# theremin.net
KiCad netlist of a schematic drawn in Altium Designer
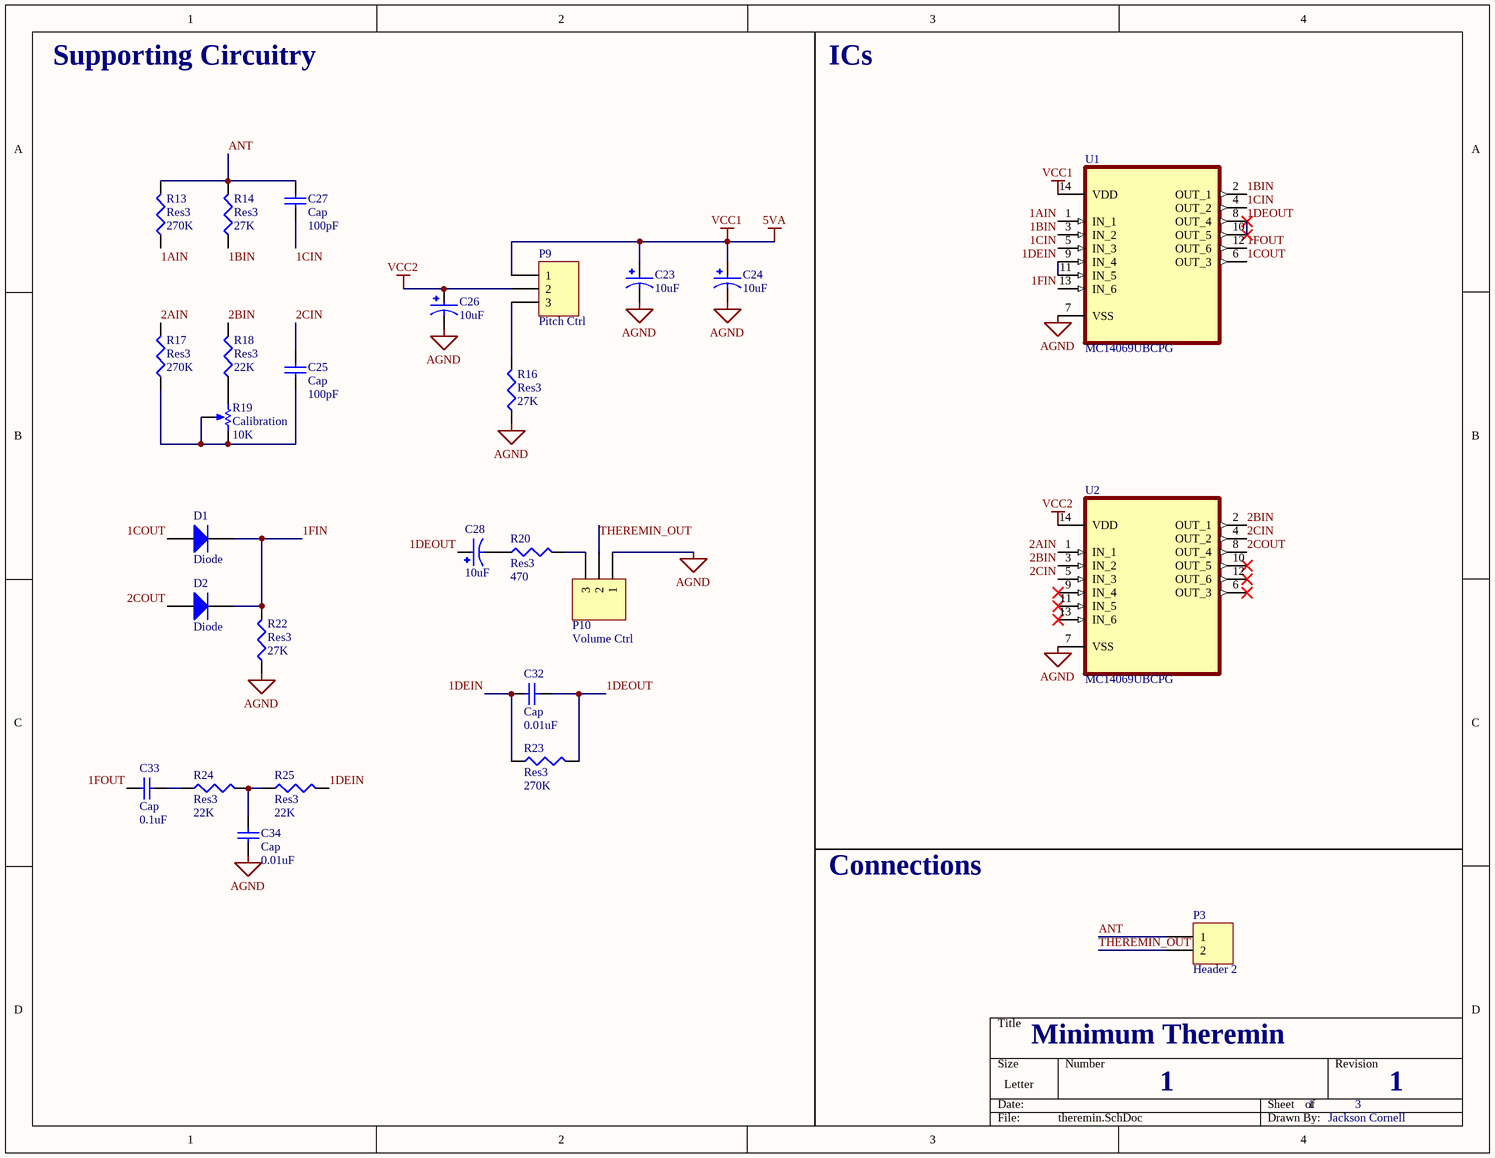
[diagram p0: theremin.SchDoc]

(export (version "E")
  (design (tool "Eeschema 10.0.6"))
  (components
    (comp (ref "C23")
      (value "10uF")
      (footprint "CAPPRD500W60D1000H1250")
      (description "Aluminum Electrolytic Capacitors - Radial Leaded")
      (fields (field (name "MP") "EEU-FC1V221E") (field (name "MF") "Panasonic"))
      (libsource (lib "") (part "EEUFC1V221E_1"))
    )
    (comp (ref "C24")
      (value "10uF")
      (footprint "CAPPRD500W60D1000H1250")
      (description "Aluminum Electrolytic Capacitors - Radial Leaded")
      (fields (field (name "MP") "EEU-FC1V221E") (field (name "MF") "Panasonic"))
      (libsource (lib "") (part "EEUFC1V221E_1"))
    )
    (comp (ref "C25")
      (value "Cap")
      (footprint "Passives:CAPC0805")
      (description "Capacitor")
      (fields (field (name "ALTIUM_VALUE") "100pF") (field (name "PUBLISHER") "Altium Limited"))
      (libsource (lib "Miscellaneous Devices") (part "Cap"))
    )
    (comp (ref "C26")
      (value "10uF")
      (footprint "CAPPRD500W60D1000H1250")
      (description "Aluminum Electrolytic Capacitors - Radial Leaded")
      (fields (field (name "MP") "EEU-FC1V221E") (field (name "MF") "Panasonic"))
      (libsource (lib "") (part "EEUFC1V221E_1"))
    )
    (comp (ref "C27")
      (value "Cap")
      (footprint "Passives:CAPC0805")
      (description "Capacitor")
      (fields (field (name "ALTIUM_VALUE") "100pF") (field (name "PUBLISHER") "Altium Limited"))
      (libsource (lib "Miscellaneous Devices") (part "Cap"))
    )
    (comp (ref "C28")
      (value "10uF")
      (footprint "CAPPRD500W60D1000H1250")
      (description "Aluminum Electrolytic Capacitors - Radial Leaded")
      (fields (field (name "MP") "EEU-FC1V221E") (field (name "MF") "Panasonic"))
      (libsource (lib "EEUFC1V221E") (part "EEUFC1V221E"))
    )
    (comp (ref "C32")
      (value "Cap")
      (footprint "Passives:CAPC0805")
      (description "Capacitor")
      (fields (field (name "ALTIUM_VALUE") "0.01uF") (field (name "PUBLISHER") "Altium Limited"))
      (libsource (lib "Miscellaneous Devices") (part "Cap"))
    )
    (comp (ref "C33")
      (value "Cap")
      (footprint "Passives:CAPC0805")
      (description "Capacitor")
      (fields (field (name "ALTIUM_VALUE") "0.1uF") (field (name "PUBLISHER") "Altium Limited"))
      (libsource (lib "Miscellaneous Devices") (part "Cap"))
    )
    (comp (ref "C34")
      (value "Cap")
      (footprint "Passives:CAPC0805")
      (description "Capacitor")
      (fields (field (name "ALTIUM_VALUE") "0.01uF") (field (name "PUBLISHER") "Altium Limited"))
      (libsource (lib "Miscellaneous Devices") (part "Cap"))
    )
    (comp (ref "D1")
      (value "Diode")
      (footprint "SMC")
      (description "Default Diode")
      (fields (field (name "PUBLISHER") "Altium Limited"))
      (libsource (lib "Miscellaneous Devices") (part "Diode"))
    )
    (comp (ref "D2")
      (value "Diode")
      (footprint "SMC")
      (description "Default Diode")
      (fields (field (name "PUBLISHER") "Altium Limited"))
      (libsource (lib "Miscellaneous Devices") (part "Diode"))
    )
    (comp (ref "P3")
      (value "Header 2")
      (footprint "HDR1X2")
      (description "Header, 2-Pin")
      (fields (field (name "PUBLISHER") "Altium Limited"))
      (libsource (lib "Miscellaneous Connectors") (part "Header 2"))
    )
    (comp (ref "P9")
      (value "Pitch Ctrl")
      (footprint "HDR1X3")
      (description "Header, 3-Pin")
      (fields (field (name "PUBLISHER") "Altium Limited"))
      (libsource (lib "Miscellaneous Connectors") (part "Header 3"))
    )
    (comp (ref "P10")
      (value "Volume Ctrl")
      (footprint "HDR1X3")
      (description "Header, 3-Pin")
      (fields (field (name "PUBLISHER") "Altium Limited"))
      (libsource (lib "") (part "Header 3_1"))
    )
    (comp (ref "R13")
      (value "Res3")
      (footprint "Passives:RES0805")
      (description "Resistor")
      (fields (field (name "ALTIUM_VALUE") "270K") (field (name "PUBLISHER") "Altium Limited"))
      (libsource (lib "Miscellaneous Devices") (part "Res3"))
    )
    (comp (ref "R14")
      (value "Res3")
      (footprint "Passives:RES0805")
      (description "Resistor")
      (fields (field (name "ALTIUM_VALUE") "27K") (field (name "PUBLISHER") "Altium Limited"))
      (libsource (lib "Miscellaneous Devices") (part "Res3"))
    )
    (comp (ref "R16")
      (value "Res3")
      (footprint "Passives:RES0805")
      (description "Resistor")
      (fields (field (name "ALTIUM_VALUE") "27K") (field (name "PUBLISHER") "Altium Limited"))
      (libsource (lib "Miscellaneous Devices") (part "Res3"))
    )
    (comp (ref "R17")
      (value "Res3")
      (footprint "Passives:RES0805")
      (description "Resistor")
      (fields (field (name "ALTIUM_VALUE") "270K") (field (name "PUBLISHER") "Altium Limited"))
      (libsource (lib "Miscellaneous Devices") (part "Res3"))
    )
    (comp (ref "R18")
      (value "Res3")
      (footprint "Passives:RES0805")
      (description "Resistor")
      (fields (field (name "ALTIUM_VALUE") "22K") (field (name "PUBLISHER") "Altium Limited"))
      (libsource (lib "Miscellaneous Devices") (part "Res3"))
    )
    (comp (ref "R19")
      (value "Calibration")
      (footprint "VR5")
      (description "Potentiometer")
      (fields (field (name "ALTIUM_VALUE") "10K") (field (name "PUBLISHER") "Altium Limited"))
      (libsource (lib "Miscellaneous Devices") (part "RPot"))
    )
    (comp (ref "R20")
      (value "Res3")
      (footprint "Passives:RES0805")
      (description "Resistor")
      (fields (field (name "ALTIUM_VALUE") "470") (field (name "PUBLISHER") "Altium Limited"))
      (libsource (lib "Miscellaneous Devices") (part "Res3"))
    )
    (comp (ref "R22")
      (value "Res3")
      (footprint "Passives:RES0805")
      (description "Resistor")
      (fields (field (name "ALTIUM_VALUE") "27K") (field (name "PUBLISHER") "Altium Limited"))
      (libsource (lib "Miscellaneous Devices") (part "Res3"))
    )
    (comp (ref "R23")
      (value "Res3")
      (footprint "Passives:RES0805")
      (description "Resistor")
      (fields (field (name "ALTIUM_VALUE") "270K") (field (name "PUBLISHER") "Altium Limited"))
      (libsource (lib "Miscellaneous Devices") (part "Res3"))
    )
    (comp (ref "R24")
      (value "Res3")
      (footprint "Passives:RES0805")
      (description "Resistor")
      (fields (field (name "ALTIUM_VALUE") "22K") (field (name "PUBLISHER") "Altium Limited"))
      (libsource (lib "Miscellaneous Devices") (part "Res3"))
    )
    (comp (ref "R25")
      (value "Res3")
      (footprint "Passives:RES0805")
      (description "Resistor")
      (fields (field (name "ALTIUM_VALUE") "22K") (field (name "PUBLISHER") "Altium Limited"))
      (libsource (lib "Miscellaneous Devices") (part "Res3"))
    )
    (comp (ref "U1")
      (value "MC14069UBCPG")
      (footprint "DIP254P762X469-14")
      (description "Inverter IC 6 Channel - 14-PDIP")
      (fields (field (name "MF") "ON Semiconductor"))
      (libsource (lib "MC14069UBCPG") (part "MC14069UBCPG"))
    )
    (comp (ref "U2")
      (value "MC14069UBCPG")
      (footprint "DIP254P762X469-14")
      (description "Inverter IC 6 Channel - 14-PDIP")
      (fields (field (name "MF") "ON Semiconductor"))
      (libsource (lib "MC14069UBCPG") (part "MC14069UBCPG"))
    )
  )
  (nets
    (net (code "1") (name "/1AIN") (class "Default")
      (node (ref "R13") (pin "1") (pinfunction "1_1") (pintype "passive"))
      (node (ref "U1") (pin "1") (pinfunction "IN_1_1") (pintype "input"))
    )
    (net (code "2") (name "/1BIN") (class "Default")
      (node (ref "R14") (pin "1") (pinfunction "1_1") (pintype "passive"))
      (node (ref "U1") (pin "2") (pinfunction "OUT_1_2") (pintype "output"))
      (node (ref "U1") (pin "3") (pinfunction "IN_2_3") (pintype "input"))
    )
    (net (code "3") (name "/1CIN") (class "Default")
      (node (ref "C27") (pin "1") (pinfunction "1_1") (pintype "passive"))
      (node (ref "U1") (pin "4") (pinfunction "OUT_2_4") (pintype "output"))
      (node (ref "U1") (pin "5") (pinfunction "IN_3_5") (pintype "input"))
    )
    (net (code "4") (name "/1COUT") (class "Default")
      (node (ref "D1") (pin "1") (pinfunction "A_1") (pintype "passive"))
      (node (ref "U1") (pin "6") (pinfunction "OUT_3_6") (pintype "output"))
    )
    (net (code "5") (name "/1DEIN") (class "Default")
      (node (ref "C32") (pin "1") (pinfunction "1_1") (pintype "passive"))
      (node (ref "R23") (pin "1") (pinfunction "1_1") (pintype "passive"))
      (node (ref "R25") (pin "2") (pinfunction "2_2") (pintype "passive"))
      (node (ref "U1") (pin "11") (pinfunction "IN_5_11") (pintype "input"))
      (node (ref "U1") (pin "9") (pinfunction "IN_4_9") (pintype "input"))
    )
    (net (code "6") (name "/1DEOUT") (class "Default")
      (node (ref "C28") (pin "P") (pinfunction "P_P") (pintype "passive"))
      (node (ref "C32") (pin "2") (pinfunction "2_2") (pintype "passive"))
      (node (ref "R23") (pin "2") (pinfunction "2_2") (pintype "passive"))
      (node (ref "U1") (pin "10") (pinfunction "OUT_5_10") (pintype "output"))
      (node (ref "U1") (pin "8") (pinfunction "OUT_4_8") (pintype "output"))
    )
    (net (code "7") (name "/1FIN") (class "Default")
      (node (ref "D1") (pin "2") (pinfunction "K_2") (pintype "passive"))
      (node (ref "D2") (pin "2") (pinfunction "K_2") (pintype "passive"))
      (node (ref "R22") (pin "2") (pinfunction "2_2") (pintype "passive"))
      (node (ref "U1") (pin "13") (pinfunction "IN_6_13") (pintype "input"))
    )
    (net (code "8") (name "/1FOUT") (class "Default")
      (node (ref "C33") (pin "1") (pinfunction "1_1") (pintype "passive"))
      (node (ref "U1") (pin "12") (pinfunction "OUT_6_12") (pintype "output"))
    )
    (net (code "9") (name "/2AIN") (class "Default")
      (node (ref "R17") (pin "2") (pinfunction "2_2") (pintype "passive"))
      (node (ref "U2") (pin "1") (pinfunction "IN_1_1") (pintype "input"))
    )
    (net (code "10") (name "/2BIN") (class "Default")
      (node (ref "R18") (pin "2") (pinfunction "2_2") (pintype "passive"))
      (node (ref "U2") (pin "2") (pinfunction "OUT_1_2") (pintype "output"))
      (node (ref "U2") (pin "3") (pinfunction "IN_2_3") (pintype "input"))
    )
    (net (code "11") (name "/2CIN") (class "Default")
      (node (ref "C25") (pin "2") (pinfunction "2_2") (pintype "passive"))
      (node (ref "U2") (pin "4") (pinfunction "OUT_2_4") (pintype "output"))
      (node (ref "U2") (pin "5") (pinfunction "IN_3_5") (pintype "input"))
    )
    (net (code "12") (name "/2COUT") (class "Default")
      (node (ref "D2") (pin "1") (pinfunction "A_1") (pintype "passive"))
      (node (ref "U2") (pin "8") (pinfunction "OUT_4_8") (pintype "output"))
    )
    (net (code "13") (name "/ANT") (class "Default")
      (node (ref "C27") (pin "2") (pinfunction "2_2") (pintype "passive"))
      (node (ref "P3") (pin "1") (pinfunction "1_1") (pintype "passive"))
      (node (ref "R13") (pin "2") (pinfunction "2_2") (pintype "passive"))
      (node (ref "R14") (pin "2") (pinfunction "2_2") (pintype "passive"))
    )
    (net (code "14") (name "/THEREMIN_OUT") (class "Default")
      (node (ref "P10") (pin "2") (pinfunction "2_2") (pintype "passive"))
      (node (ref "P3") (pin "2") (pinfunction "2_2") (pintype "passive"))
    )
    (net (code "15") (name "5VA") (class "Default")
      (node (ref "C23") (pin "P") (pinfunction "P_P") (pintype "passive"))
      (node (ref "C24") (pin "P") (pinfunction "P_P") (pintype "passive"))
      (node (ref "P9") (pin "1") (pinfunction "1_1") (pintype "passive"))
      (node (ref "U1") (pin "14") (pinfunction "VDD_14") (pintype "power_in"))
    )
    (net (code "16") (name "AGND") (class "Default")
      (node (ref "C23") (pin "N") (pinfunction "N_N") (pintype "passive"))
      (node (ref "C24") (pin "N") (pinfunction "N_N") (pintype "passive"))
      (node (ref "C26") (pin "N") (pinfunction "N_N") (pintype "passive"))
      (node (ref "C34") (pin "1") (pinfunction "1_1") (pintype "passive"))
      (node (ref "P10") (pin "1") (pinfunction "1_1") (pintype "passive"))
      (node (ref "R16") (pin "1") (pinfunction "1_1") (pintype "passive"))
      (node (ref "R22") (pin "1") (pinfunction "1_1") (pintype "passive"))
      (node (ref "U1") (pin "7") (pinfunction "VSS_7") (pintype "power_in"))
      (node (ref "U2") (pin "7") (pinfunction "VSS_7") (pintype "power_in"))
    )
    (net (code "17") (name "Net-(C28-PadN)") (class "Default")
      (node (ref "C28") (pin "N") (pinfunction "N_N") (pintype "passive"))
      (node (ref "R20") (pin "1") (pinfunction "1_1") (pintype "passive"))
    )
    (net (code "18") (name "Net-(C33-Pad2)") (class "Default")
      (node (ref "C33") (pin "2") (pinfunction "2_2") (pintype "passive"))
      (node (ref "R24") (pin "1") (pinfunction "1_1") (pintype "passive"))
    )
    (net (code "19") (name "Net-(C34-Pad2)") (class "Default")
      (node (ref "C34") (pin "2") (pinfunction "2_2") (pintype "passive"))
      (node (ref "R24") (pin "2") (pinfunction "2_2") (pintype "passive"))
      (node (ref "R25") (pin "1") (pinfunction "1_1") (pintype "passive"))
    )
    (net (code "20") (name "Net-(P9-Pad3)") (class "Default")
      (node (ref "P9") (pin "3") (pinfunction "3_3") (pintype "passive"))
      (node (ref "R16") (pin "2") (pinfunction "2_2") (pintype "passive"))
    )
    (net (code "21") (name "Net-(P10-Pad3)") (class "Default")
      (node (ref "P10") (pin "3") (pinfunction "3_3") (pintype "passive"))
      (node (ref "R20") (pin "2") (pinfunction "2_2") (pintype "passive"))
    )
    (net (code "22") (name "Net-(R19-BOT)") (class "Default")
      (node (ref "C25") (pin "1") (pinfunction "1_1") (pintype "passive"))
      (node (ref "R17") (pin "1") (pinfunction "1_1") (pintype "passive"))
      (node (ref "R19") (pin "2") (pinfunction "BOT_2") (pintype "passive"))
      (node (ref "R19") (pin "3") (pinfunction "TAP_3") (pintype "passive"))
    )
    (net (code "23") (name "Net-(R19-TOP)") (class "Default")
      (node (ref "R18") (pin "1") (pinfunction "1_1") (pintype "passive"))
      (node (ref "R19") (pin "1") (pinfunction "TOP_1") (pintype "passive"))
    )
    (net (code "24") (name "VCC2") (class "Default")
      (node (ref "C26") (pin "P") (pinfunction "P_P") (pintype "passive"))
      (node (ref "P9") (pin "2") (pinfunction "2_2") (pintype "passive"))
      (node (ref "U2") (pin "14") (pinfunction "VDD_14") (pintype "power_in"))
    )
    (net (code "25") (name "unconnected-(U2-IN_4-Pad9)") (class "Default")
      (node (ref "U2") (pin "9") (pinfunction "IN_4_9") (pintype "input+no_connect"))
    )
    (net (code "26") (name "unconnected-(U2-IN_5-Pad11)") (class "Default")
      (node (ref "U2") (pin "11") (pinfunction "IN_5_11") (pintype "input+no_connect"))
    )
    (net (code "27") (name "unconnected-(U2-IN_6-Pad13)") (class "Default")
      (node (ref "U2") (pin "13") (pinfunction "IN_6_13") (pintype "input+no_connect"))
    )
    (net (code "28") (name "unconnected-(U2-OUT_3-Pad6)") (class "Default")
      (node (ref "U2") (pin "6") (pinfunction "OUT_3_6") (pintype "output+no_connect"))
    )
    (net (code "29") (name "unconnected-(U2-OUT_5-Pad10)") (class "Default")
      (node (ref "U2") (pin "10") (pinfunction "OUT_5_10") (pintype "output+no_connect"))
    )
    (net (code "30") (name "unconnected-(U2-OUT_6-Pad12)") (class "Default")
      (node (ref "U2") (pin "12") (pinfunction "OUT_6_12") (pintype "output+no_connect"))
    )
  )
)
